# kanal_v1.net
KiCad netlist of a schematic drawn in EAGLE
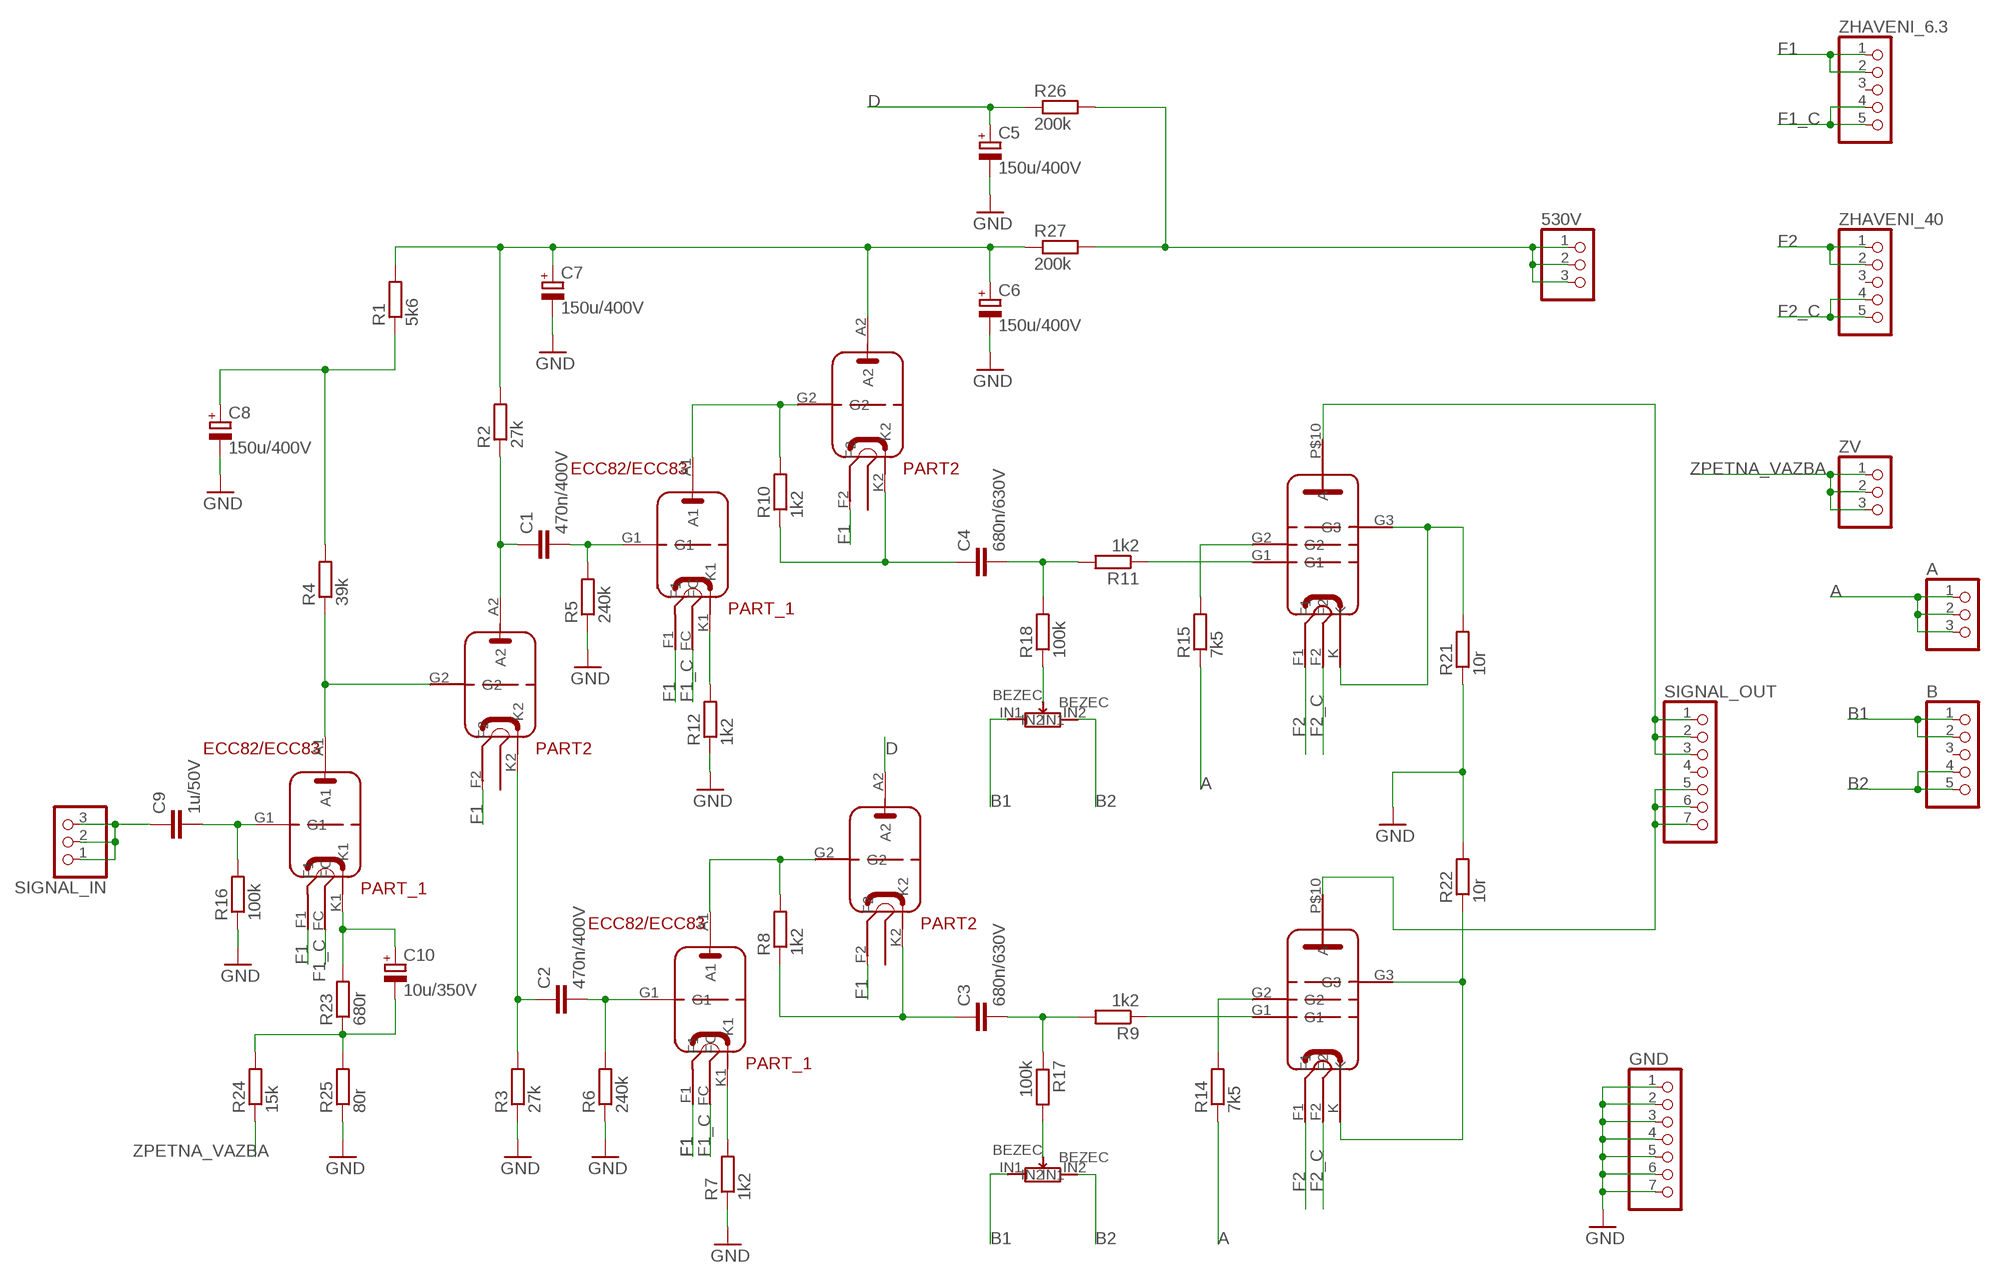
[diagram p0: schematic, sheet 1]

(export (version "E")
  (design (tool "Eeschema 10.0.6"))
  (components
    (comp (ref "530V")
      (value "PINHD-1X3")
      (footprint "eagle-import:1X03")
      (libsource (lib "eagle-import") (part "PINHD-1X3"))
    )
    (comp (ref "A")
      (value "PINHD-1X3")
      (footprint "eagle-import:1X03")
      (libsource (lib "eagle-import") (part "PINHD-1X3"))
    )
    (comp (ref "B")
      (value "PINHD-1X5")
      (footprint "eagle-import:1X05")
      (libsource (lib "eagle-import") (part "PINHD-1X5"))
    )
    (comp (ref "C1")
      (value "470n/400V")
      (footprint "eagle-import:C15B7")
      (libsource (lib "eagle-import") (part "C15/7"))
    )
    (comp (ref "C2")
      (value "470n/400V")
      (footprint "eagle-import:C15B7")
      (libsource (lib "eagle-import") (part "C15/7"))
    )
    (comp (ref "C3")
      (value "680n/630V")
      (footprint "eagle-import:C27.5B11")
      (libsource (lib "eagle-import") (part "C27/11"))
    )
    (comp (ref "C4")
      (value "680n/630V")
      (footprint "eagle-import:C27.5B11")
      (libsource (lib "eagle-import") (part "C27/11"))
    )
    (comp (ref "C5")
      (value "150u/400V")
      (footprint "eagle-import:EB25D")
      (libsource (lib "eagle-import") (part "resistor_CPOL-EUE10-25"))
    )
    (comp (ref "C6")
      (value "150u/400V")
      (footprint "eagle-import:EB25D")
      (libsource (lib "eagle-import") (part "resistor_CPOL-EUE10-25"))
    )
    (comp (ref "C7")
      (value "150u/400V")
      (footprint "eagle-import:EB25D")
      (libsource (lib "eagle-import") (part "resistor_CPOL-EUE10-25"))
    )
    (comp (ref "C8")
      (value "150u/400V")
      (footprint "eagle-import:EB25D")
      (libsource (lib "eagle-import") (part "resistor_CPOL-EUE10-25"))
    )
    (comp (ref "C9")
      (value "1u/50V")
      (footprint "eagle-import:C5B3.5")
      (libsource (lib "eagle-import") (part "C5/3.5"))
    )
    (comp (ref "C10")
      (value "10u/350V")
      (footprint "eagle-import:E5-10,5")
      (libsource (lib "eagle-import") (part "CPOL-EUE5-10.5"))
    )
    (comp (ref "GND")
      (value "PINHD-1X7")
      (footprint "eagle-import:1X07")
      (libsource (lib "eagle-import") (part "PINHD-1X7"))
    )
    (comp (ref "R1")
      (value "5k6")
      (footprint "eagle-import:0309_10")
      (libsource (lib "eagle-import") (part "R-EU_0309/10"))
    )
    (comp (ref "R2")
      (value "27k")
      (footprint "eagle-import:0309_10")
      (libsource (lib "eagle-import") (part "R-EU_0309/10"))
    )
    (comp (ref "R3")
      (value "27k")
      (footprint "eagle-import:0309_10")
      (libsource (lib "eagle-import") (part "R-EU_0309/10"))
    )
    (comp (ref "R4")
      (value "39k")
      (footprint "eagle-import:0309_10")
      (libsource (lib "eagle-import") (part "R-EU_0309/10"))
    )
    (comp (ref "R5")
      (value "240k")
      (footprint "eagle-import:0309_10")
      (libsource (lib "eagle-import") (part "R-EU_0309/10"))
    )
    (comp (ref "R6")
      (value "240k")
      (footprint "eagle-import:0309_10")
      (libsource (lib "eagle-import") (part "R-EU_0309/10"))
    )
    (comp (ref "R7")
      (value "1k2")
      (footprint "eagle-import:0309_10")
      (libsource (lib "eagle-import") (part "R-EU_0309/10"))
    )
    (comp (ref "R8")
      (value "1k2")
      (footprint "eagle-import:0309_10")
      (libsource (lib "eagle-import") (part "R-EU_0309/10"))
    )
    (comp (ref "R9")
      (value "1k2")
      (footprint "eagle-import:0309_10")
      (libsource (lib "eagle-import") (part "R-EU_0309/10"))
    )
    (comp (ref "R10")
      (value "1k2")
      (footprint "eagle-import:0309_10")
      (libsource (lib "eagle-import") (part "R-EU_0309/10"))
    )
    (comp (ref "R11")
      (value "1k2")
      (footprint "eagle-import:0309_10")
      (libsource (lib "eagle-import") (part "R-EU_0309/10"))
    )
    (comp (ref "R12")
      (value "1k2")
      (footprint "eagle-import:0309_10")
      (libsource (lib "eagle-import") (part "R-EU_0309/10"))
    )
    (comp (ref "R14")
      (value "7k5")
      (footprint "eagle-import:0309_10")
      (libsource (lib "eagle-import") (part "R-EU_0309/10"))
    )
    (comp (ref "R15")
      (value "7k5")
      (footprint "eagle-import:0309_10")
      (libsource (lib "eagle-import") (part "R-EU_0309/10"))
    )
    (comp (ref "R16")
      (value "100k")
      (footprint "eagle-import:0309_10")
      (libsource (lib "eagle-import") (part "R-EU_0309/10"))
    )
    (comp (ref "R17")
      (value "100k")
      (footprint "eagle-import:0309_10")
      (libsource (lib "eagle-import") (part "R-EU_0309/10"))
    )
    (comp (ref "R18")
      (value "100k")
      (footprint "eagle-import:0309_10")
      (libsource (lib "eagle-import") (part "R-EU_0309/10"))
    )
    (comp (ref "R21")
      (value "10r")
      (footprint "eagle-import:0309_10")
      (libsource (lib "eagle-import") (part "R-EU_0309/10"))
    )
    (comp (ref "R22")
      (value "10r")
      (footprint "eagle-import:0309_10")
      (libsource (lib "eagle-import") (part "R-EU_0309/10"))
    )
    (comp (ref "R23")
      (value "680r")
      (footprint "eagle-import:0309_10")
      (libsource (lib "eagle-import") (part "R-EU_0309/10"))
    )
    (comp (ref "R24")
      (value "15k")
      (footprint "eagle-import:0309_10")
      (libsource (lib "eagle-import") (part "R-EU_0309/10"))
    )
    (comp (ref "R25")
      (value "80r")
      (footprint "eagle-import:0309_10")
      (libsource (lib "eagle-import") (part "R-EU_0309/10"))
    )
    (comp (ref "R26")
      (value "200k")
      (footprint "eagle-import:0309_10")
      (libsource (lib "eagle-import") (part "R-EU_0309/10"))
    )
    (comp (ref "R27")
      (value "200k")
      (footprint "eagle-import:0309_10")
      (libsource (lib "eagle-import") (part "R-EU_0309/10"))
    )
    (comp (ref "SIGNAL_IN")
      (value "PINHD-1X3")
      (footprint "eagle-import:1X03")
      (libsource (lib "eagle-import") (part "PINHD-1X3"))
    )
    (comp (ref "SIGNAL_OUT")
      (value "PINHD-1X7")
      (footprint "eagle-import:1X07")
      (libsource (lib "eagle-import") (part "PINHD-1X7"))
    )
    (comp (ref "U$1")
      (value "ECC82")
      (footprint "eagle-import:ECC82_PACKAGE")
      (libsource (lib "eagle-import") (part "ECC82"))
    )
    (comp (ref "U$2")
      (value "ECC83")
      (footprint "eagle-import:ECC82_PACKAGE")
      (libsource (lib "eagle-import") (part "ECC83"))
    )
    (comp (ref "U$3")
      (value "ECC83")
      (footprint "eagle-import:ECC82_PACKAGE")
      (libsource (lib "eagle-import") (part "ECC83"))
    )
    (comp (ref "U$4")
      (value "PL509")
      (footprint "eagle-import:PL509_PACKAGE")
      (libsource (lib "eagle-import") (part "PL509"))
    )
    (comp (ref "U$5")
      (value "PL509")
      (footprint "eagle-import:PL509_PACKAGE")
      (libsource (lib "eagle-import") (part "PL509"))
    )
    (comp (ref "U$6")
      (value "TRIMMER")
      (footprint "eagle-import:TRIMMER_15X15_PACKAGE")
      (libsource (lib "eagle-import") (part "TRIMMER"))
    )
    (comp (ref "U$7")
      (value "TRIMMER")
      (footprint "eagle-import:TRIMMER_15X15_PACKAGE")
      (libsource (lib "eagle-import") (part "TRIMMER"))
    )
    (comp (ref "ZHAVENI_6.3")
      (value "PINHD-1X5")
      (footprint "eagle-import:1X05")
      (libsource (lib "eagle-import") (part "PINHD-1X5"))
    )
    (comp (ref "ZHAVENI_40")
      (value "PINHD-1X5")
      (footprint "eagle-import:1X05")
      (libsource (lib "eagle-import") (part "PINHD-1X5"))
    )
    (comp (ref "ZV")
      (value "PINHD-1X3")
      (footprint "eagle-import:1X03")
      (libsource (lib "eagle-import") (part "PINHD-1X3"))
    )
  )
  (nets
    (net (code "1") (name "/A") (class "Default")
      (node (ref "A") (pin "1") (pinfunction "1_1") (pintype "passive"))
      (node (ref "A") (pin "2") (pinfunction "2_2") (pintype "passive"))
      (node (ref "A") (pin "3") (pinfunction "3_3") (pintype "passive"))
      (node (ref "R14") (pin "1") (pinfunction "1_1") (pintype "passive"))
      (node (ref "R15") (pin "1") (pinfunction "1_1") (pintype "passive"))
    )
    (net (code "2") (name "/B1") (class "Default")
      (node (ref "B") (pin "1") (pinfunction "1_1") (pintype "passive"))
      (node (ref "B") (pin "2") (pinfunction "2_2") (pintype "passive"))
      (node (ref "U$6") (pin "IN1") (pinfunction "IN1_IN1") (pintype "bidirectional"))
      (node (ref "U$7") (pin "IN1") (pinfunction "IN1_IN1") (pintype "bidirectional"))
    )
    (net (code "3") (name "/B2") (class "Default")
      (node (ref "B") (pin "4") (pinfunction "4_4") (pintype "passive"))
      (node (ref "B") (pin "5") (pinfunction "5_5") (pintype "passive"))
      (node (ref "U$6") (pin "IN2") (pinfunction "IN2_IN2") (pintype "bidirectional"))
      (node (ref "U$7") (pin "IN2") (pinfunction "IN2_IN2") (pintype "bidirectional"))
    )
    (net (code "4") (name "/D") (class "Default")
      (node (ref "C5") (pin "+") (pinfunction "+_+") (pintype "passive"))
      (node (ref "R26") (pin "1") (pinfunction "1_1") (pintype "passive"))
      (node (ref "U$3") (pin "A2") (pinfunction "A2_A2") (pintype "bidirectional"))
    )
    (net (code "5") (name "/F1") (class "Default")
      (node (ref "U$1") (pin "F1") (pinfunction "F1_F1") (pintype "bidirectional"))
      (node (ref "U$1") (pin "F2") (pinfunction "F2_F2") (pintype "bidirectional"))
      (node (ref "U$2") (pin "F1") (pinfunction "F1_F1") (pintype "bidirectional"))
      (node (ref "U$2") (pin "F2") (pinfunction "F2_F2") (pintype "bidirectional"))
      (node (ref "U$3") (pin "F1") (pinfunction "F1_F1") (pintype "bidirectional"))
      (node (ref "U$3") (pin "F2") (pinfunction "F2_F2") (pintype "bidirectional"))
      (node (ref "ZHAVENI_6.3") (pin "1") (pinfunction "1_1") (pintype "passive"))
      (node (ref "ZHAVENI_6.3") (pin "2") (pinfunction "2_2") (pintype "passive"))
    )
    (net (code "6") (name "/F1_C") (class "Default")
      (node (ref "U$1") (pin "FC") (pinfunction "FC_FC") (pintype "bidirectional"))
      (node (ref "U$2") (pin "FC") (pinfunction "FC_FC") (pintype "bidirectional"))
      (node (ref "U$3") (pin "FC") (pinfunction "FC_FC") (pintype "bidirectional"))
      (node (ref "ZHAVENI_6.3") (pin "4") (pinfunction "4_4") (pintype "passive"))
      (node (ref "ZHAVENI_6.3") (pin "5") (pinfunction "5_5") (pintype "passive"))
    )
    (net (code "7") (name "/F2") (class "Default")
      (node (ref "U$4") (pin "F1") (pinfunction "F1_F1") (pintype "bidirectional"))
      (node (ref "U$5") (pin "F1") (pinfunction "F1_F1") (pintype "bidirectional"))
      (node (ref "ZHAVENI_40") (pin "1") (pinfunction "1_1") (pintype "passive"))
      (node (ref "ZHAVENI_40") (pin "2") (pinfunction "2_2") (pintype "passive"))
    )
    (net (code "8") (name "/F2_C") (class "Default")
      (node (ref "U$4") (pin "F2") (pinfunction "F2_F2") (pintype "bidirectional"))
      (node (ref "U$5") (pin "F2") (pinfunction "F2_F2") (pintype "bidirectional"))
      (node (ref "ZHAVENI_40") (pin "4") (pinfunction "4_4") (pintype "passive"))
      (node (ref "ZHAVENI_40") (pin "5") (pinfunction "5_5") (pintype "passive"))
    )
    (net (code "9") (name "/ZPETNA_VAZBA") (class "Default")
      (node (ref "R24") (pin "1") (pinfunction "1_1") (pintype "passive"))
      (node (ref "ZV") (pin "1") (pinfunction "1_1") (pintype "passive"))
      (node (ref "ZV") (pin "2") (pinfunction "2_2") (pintype "passive"))
      (node (ref "ZV") (pin "3") (pinfunction "3_3") (pintype "passive"))
    )
    (net (code "10") (name "GND") (class "Default")
      (node (ref "C5") (pin "-") (pinfunction "-_-") (pintype "passive"))
      (node (ref "C6") (pin "-") (pinfunction "-_-") (pintype "passive"))
      (node (ref "C7") (pin "-") (pinfunction "-_-") (pintype "passive"))
      (node (ref "C8") (pin "-") (pinfunction "-_-") (pintype "passive"))
      (node (ref "GND") (pin "1") (pinfunction "1_1") (pintype "passive"))
      (node (ref "GND") (pin "2") (pinfunction "2_2") (pintype "passive"))
      (node (ref "GND") (pin "3") (pinfunction "3_3") (pintype "passive"))
      (node (ref "GND") (pin "4") (pinfunction "4_4") (pintype "passive"))
      (node (ref "GND") (pin "5") (pinfunction "5_5") (pintype "passive"))
      (node (ref "GND") (pin "6") (pinfunction "6_6") (pintype "passive"))
      (node (ref "GND") (pin "7") (pinfunction "7_7") (pintype "passive"))
      (node (ref "R12") (pin "1") (pinfunction "1_1") (pintype "passive"))
      (node (ref "R16") (pin "1") (pinfunction "1_1") (pintype "passive"))
      (node (ref "R21") (pin "1") (pinfunction "1_1") (pintype "passive"))
      (node (ref "R22") (pin "2") (pinfunction "2_2") (pintype "passive"))
      (node (ref "R25") (pin "1") (pinfunction "1_1") (pintype "passive"))
      (node (ref "R3") (pin "1") (pinfunction "1_1") (pintype "passive"))
      (node (ref "R5") (pin "1") (pinfunction "1_1") (pintype "passive"))
      (node (ref "R6") (pin "1") (pinfunction "1_1") (pintype "passive"))
      (node (ref "R7") (pin "1") (pinfunction "1_1") (pintype "passive"))
    )
    (net (code "11") (name "Net-(530V-Pad1)") (class "Default")
      (node (ref "530V") (pin "1") (pinfunction "1_1") (pintype "passive"))
      (node (ref "530V") (pin "2") (pinfunction "2_2") (pintype "passive"))
      (node (ref "530V") (pin "3") (pinfunction "3_3") (pintype "passive"))
      (node (ref "R26") (pin "2") (pinfunction "2_2") (pintype "passive"))
      (node (ref "R27") (pin "2") (pinfunction "2_2") (pintype "passive"))
    )
    (net (code "12") (name "Net-(C1-Pad1)") (class "Default")
      (node (ref "C1") (pin "1") (pinfunction "1_1") (pintype "passive"))
      (node (ref "R2") (pin "1") (pinfunction "1_1") (pintype "passive"))
      (node (ref "U$1") (pin "A2") (pinfunction "A2_A2") (pintype "bidirectional"))
    )
    (net (code "13") (name "Net-(C1-Pad2)") (class "Default")
      (node (ref "C1") (pin "2") (pinfunction "2_2") (pintype "passive"))
      (node (ref "R5") (pin "2") (pinfunction "2_2") (pintype "passive"))
      (node (ref "U$2") (pin "G1") (pinfunction "G1_G1") (pintype "bidirectional"))
    )
    (net (code "14") (name "Net-(C2-Pad1)") (class "Default")
      (node (ref "C2") (pin "1") (pinfunction "1_1") (pintype "passive"))
      (node (ref "R3") (pin "2") (pinfunction "2_2") (pintype "passive"))
      (node (ref "U$1") (pin "K2") (pinfunction "K2_K2") (pintype "bidirectional"))
    )
    (net (code "15") (name "Net-(C2-Pad2)") (class "Default")
      (node (ref "C2") (pin "2") (pinfunction "2_2") (pintype "passive"))
      (node (ref "R6") (pin "2") (pinfunction "2_2") (pintype "passive"))
      (node (ref "U$3") (pin "G1") (pinfunction "G1_G1") (pintype "bidirectional"))
    )
    (net (code "16") (name "Net-(C3-Pad1)") (class "Default")
      (node (ref "C3") (pin "1") (pinfunction "1_1") (pintype "passive"))
      (node (ref "R8") (pin "1") (pinfunction "1_1") (pintype "passive"))
      (node (ref "U$3") (pin "K2") (pinfunction "K2_K2") (pintype "bidirectional"))
    )
    (net (code "17") (name "Net-(C3-Pad2)") (class "Default")
      (node (ref "C3") (pin "2") (pinfunction "2_2") (pintype "passive"))
      (node (ref "R17") (pin "1") (pinfunction "1_1") (pintype "passive"))
      (node (ref "R9") (pin "2") (pinfunction "2_2") (pintype "passive"))
    )
    (net (code "18") (name "Net-(C4-Pad1)") (class "Default")
      (node (ref "C4") (pin "1") (pinfunction "1_1") (pintype "passive"))
      (node (ref "R10") (pin "1") (pinfunction "1_1") (pintype "passive"))
      (node (ref "U$2") (pin "K2") (pinfunction "K2_K2") (pintype "bidirectional"))
    )
    (net (code "19") (name "Net-(C4-Pad2)") (class "Default")
      (node (ref "C4") (pin "2") (pinfunction "2_2") (pintype "passive"))
      (node (ref "R11") (pin "2") (pinfunction "2_2") (pintype "passive"))
      (node (ref "R18") (pin "2") (pinfunction "2_2") (pintype "passive"))
    )
    (net (code "20") (name "Net-(C6-Pad+)") (class "Default")
      (node (ref "C6") (pin "+") (pinfunction "+_+") (pintype "passive"))
      (node (ref "C7") (pin "+") (pinfunction "+_+") (pintype "passive"))
      (node (ref "R1") (pin "2") (pinfunction "2_2") (pintype "passive"))
      (node (ref "R2") (pin "2") (pinfunction "2_2") (pintype "passive"))
      (node (ref "R27") (pin "1") (pinfunction "1_1") (pintype "passive"))
      (node (ref "U$2") (pin "A2") (pinfunction "A2_A2") (pintype "bidirectional"))
    )
    (net (code "21") (name "Net-(C8-Pad+)") (class "Default")
      (node (ref "C8") (pin "+") (pinfunction "+_+") (pintype "passive"))
      (node (ref "R1") (pin "1") (pinfunction "1_1") (pintype "passive"))
      (node (ref "R4") (pin "2") (pinfunction "2_2") (pintype "passive"))
    )
    (net (code "22") (name "Net-(C9-Pad1)") (class "Default")
      (node (ref "C9") (pin "1") (pinfunction "1_1") (pintype "passive"))
      (node (ref "SIGNAL_IN") (pin "1") (pinfunction "1_1") (pintype "passive"))
      (node (ref "SIGNAL_IN") (pin "2") (pinfunction "2_2") (pintype "passive"))
      (node (ref "SIGNAL_IN") (pin "3") (pinfunction "3_3") (pintype "passive"))
    )
    (net (code "23") (name "Net-(C9-Pad2)") (class "Default")
      (node (ref "C9") (pin "2") (pinfunction "2_2") (pintype "passive"))
      (node (ref "R16") (pin "2") (pinfunction "2_2") (pintype "passive"))
      (node (ref "U$1") (pin "G1") (pinfunction "G1_G1") (pintype "bidirectional"))
    )
    (net (code "24") (name "Net-(C10-Pad+)") (class "Default")
      (node (ref "C10") (pin "+") (pinfunction "+_+") (pintype "passive"))
      (node (ref "R23") (pin "2") (pinfunction "2_2") (pintype "passive"))
      (node (ref "U$1") (pin "K1") (pinfunction "K1_K1") (pintype "bidirectional"))
    )
    (net (code "25") (name "Net-(C10-Pad-)") (class "Default")
      (node (ref "C10") (pin "-") (pinfunction "-_-") (pintype "passive"))
      (node (ref "R23") (pin "1") (pinfunction "1_1") (pintype "passive"))
      (node (ref "R24") (pin "2") (pinfunction "2_2") (pintype "passive"))
      (node (ref "R25") (pin "2") (pinfunction "2_2") (pintype "passive"))
    )
    (net (code "26") (name "Net-(R4-Pad1)") (class "Default")
      (node (ref "R4") (pin "1") (pinfunction "1_1") (pintype "passive"))
      (node (ref "U$1") (pin "A1") (pinfunction "A1_A1") (pintype "bidirectional"))
      (node (ref "U$1") (pin "G2") (pinfunction "G2_G2") (pintype "bidirectional"))
    )
    (net (code "27") (name "Net-(R7-Pad2)") (class "Default")
      (node (ref "R7") (pin "2") (pinfunction "2_2") (pintype "passive"))
      (node (ref "U$3") (pin "K1") (pinfunction "K1_K1") (pintype "bidirectional"))
    )
    (net (code "28") (name "Net-(R8-Pad2)") (class "Default")
      (node (ref "R8") (pin "2") (pinfunction "2_2") (pintype "passive"))
      (node (ref "U$3") (pin "A1") (pinfunction "A1_A1") (pintype "bidirectional"))
      (node (ref "U$3") (pin "G2") (pinfunction "G2_G2") (pintype "bidirectional"))
    )
    (net (code "29") (name "Net-(R9-Pad1)") (class "Default")
      (node (ref "R9") (pin "1") (pinfunction "1_1") (pintype "passive"))
      (node (ref "U$5") (pin "G1") (pinfunction "G1_G1") (pintype "bidirectional"))
    )
    (net (code "30") (name "Net-(R10-Pad2)") (class "Default")
      (node (ref "R10") (pin "2") (pinfunction "2_2") (pintype "passive"))
      (node (ref "U$2") (pin "A1") (pinfunction "A1_A1") (pintype "bidirectional"))
      (node (ref "U$2") (pin "G2") (pinfunction "G2_G2") (pintype "bidirectional"))
    )
    (net (code "31") (name "Net-(R11-Pad1)") (class "Default")
      (node (ref "R11") (pin "1") (pinfunction "1_1") (pintype "passive"))
      (node (ref "U$4") (pin "G1") (pinfunction "G1_G1") (pintype "bidirectional"))
    )
    (net (code "32") (name "Net-(R12-Pad2)") (class "Default")
      (node (ref "R12") (pin "2") (pinfunction "2_2") (pintype "passive"))
      (node (ref "U$2") (pin "K1") (pinfunction "K1_K1") (pintype "bidirectional"))
    )
    (net (code "33") (name "Net-(R14-Pad2)") (class "Default")
      (node (ref "R14") (pin "2") (pinfunction "2_2") (pintype "passive"))
      (node (ref "U$5") (pin "G2") (pinfunction "G2_G2") (pintype "bidirectional"))
    )
    (net (code "34") (name "Net-(R15-Pad2)") (class "Default")
      (node (ref "R15") (pin "2") (pinfunction "2_2") (pintype "passive"))
      (node (ref "U$4") (pin "G2") (pinfunction "G2_G2") (pintype "bidirectional"))
    )
    (net (code "35") (name "Net-(R17-Pad2)") (class "Default")
      (node (ref "R17") (pin "2") (pinfunction "2_2") (pintype "passive"))
      (node (ref "U$6") (pin "BEZEC") (pinfunction "BEZEC_BEZEC") (pintype "bidirectional"))
    )
    (net (code "36") (name "Net-(R18-Pad1)") (class "Default")
      (node (ref "R18") (pin "1") (pinfunction "1_1") (pintype "passive"))
      (node (ref "U$7") (pin "BEZEC") (pinfunction "BEZEC_BEZEC") (pintype "bidirectional"))
    )
    (net (code "37") (name "Net-(R21-Pad2)") (class "Default")
      (node (ref "R21") (pin "2") (pinfunction "2_2") (pintype "passive"))
      (node (ref "U$4") (pin "G3") (pinfunction "G3_G3") (pintype "bidirectional"))
      (node (ref "U$4") (pin "K") (pinfunction "K_K") (pintype "bidirectional"))
    )
    (net (code "38") (name "Net-(R22-Pad1)") (class "Default")
      (node (ref "R22") (pin "1") (pinfunction "1_1") (pintype "passive"))
      (node (ref "U$5") (pin "G3") (pinfunction "G3_G3") (pintype "bidirectional"))
      (node (ref "U$5") (pin "K") (pinfunction "K_K") (pintype "bidirectional"))
    )
    (net (code "39") (name "Net-(U$4-A)") (class "Default")
      (node (ref "SIGNAL_OUT") (pin "1") (pinfunction "1_1") (pintype "passive"))
      (node (ref "SIGNAL_OUT") (pin "2") (pinfunction "2_2") (pintype "passive"))
      (node (ref "SIGNAL_OUT") (pin "3") (pinfunction "3_3") (pintype "passive"))
      (node (ref "U$4") (pin "P$10") (pinfunction "A_P$10") (pintype "bidirectional"))
    )
    (net (code "40") (name "Net-(U$5-A)") (class "Default")
      (node (ref "SIGNAL_OUT") (pin "5") (pinfunction "5_5") (pintype "passive"))
      (node (ref "SIGNAL_OUT") (pin "6") (pinfunction "6_6") (pintype "passive"))
      (node (ref "SIGNAL_OUT") (pin "7") (pinfunction "7_7") (pintype "passive"))
      (node (ref "U$5") (pin "P$10") (pinfunction "A_P$10") (pintype "bidirectional"))
    )
    (net (code "41") (name "unconnected-(B-Pad3)") (class "Default")
      (node (ref "B") (pin "3") (pinfunction "3_3") (pintype "passive"))
    )
    (net (code "42") (name "unconnected-(SIGNAL_OUT-Pad4)") (class "Default")
      (node (ref "SIGNAL_OUT") (pin "4") (pinfunction "4_4") (pintype "passive"))
    )
    (net (code "43") (name "unconnected-(ZHAVENI_6.3-Pad3)") (class "Default")
      (node (ref "ZHAVENI_6.3") (pin "3") (pinfunction "3_3") (pintype "passive"))
    )
    (net (code "44") (name "unconnected-(ZHAVENI_40-Pad3)") (class "Default")
      (node (ref "ZHAVENI_40") (pin "3") (pinfunction "3_3") (pintype "passive"))
    )
  )
)
